# SWR_Tandem_Match.net
KiCad netlist of a schematic drawn in Altium Designer
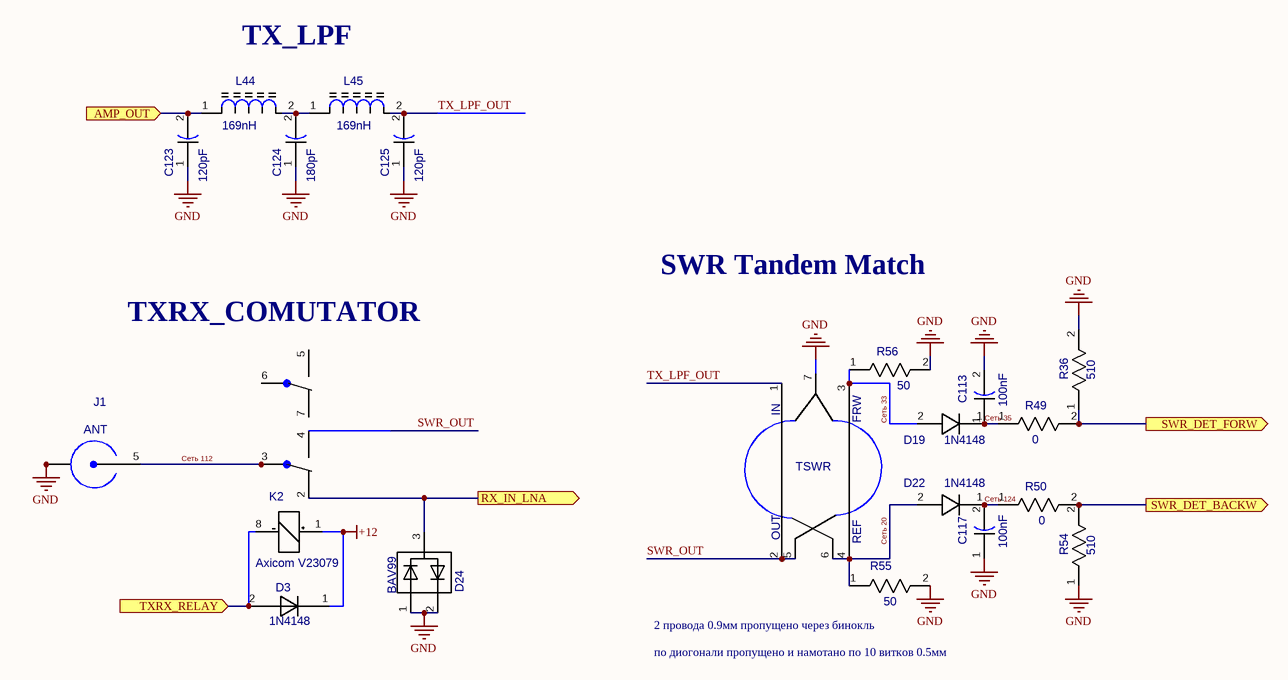
[diagram p0: SWR Tandem Match.SchDoc]

(export (version "E")
  (design (tool "Eeschema 10.0.6"))
  (components
    (comp (ref "C113")
      (value "100nF")
      (footprint "CAP_0805")
      (description "CAP_0805")
      (libsource (lib "*") (part "CAP_0805"))
    )
    (comp (ref "C117")
      (value "100nF")
      (footprint "CAP_0805")
      (description "CAP_0805")
      (libsource (lib "*") (part "CAP_0805"))
    )
    (comp (ref "C123")
      (value "120pF")
      (footprint "CAP_1206")
      (description "CAP_1206")
      (libsource (lib "*") (part "CAP_1206"))
    )
    (comp (ref "C124")
      (value "180pF")
      (footprint "CAP_1206")
      (description "CAP_1206")
      (libsource (lib "*") (part "CAP_1206"))
    )
    (comp (ref "C125")
      (value "120pF")
      (footprint "CAP_1206")
      (description "CAP_1206")
      (libsource (lib "*") (part "CAP_1206"))
    )
    (comp (ref "D3") (value "1N4148") (footprint "1N4148") (libsource (lib "*") (part "1N4148")))
    (comp (ref "D19")
      (value "1N4148")
      (footprint "DIODE_1206")
      (description "DIODE_1206")
      (libsource (lib "*") (part "DIODE_1206"))
    )
    (comp (ref "D22")
      (value "1N4148")
      (footprint "DIODE_1206")
      (description "DIODE_1206")
      (libsource (lib "*") (part "DIODE_1206"))
    )
    (comp (ref "D24") (value "BAV99") (footprint "SOT23") (libsource (lib "*") (part "BAV99")))
    (comp (ref "J1")
      (value "ANT")
      (footprint "31-5431")
      (description "31-5431")
      (libsource (lib "RF-UNIT_1") (part "31-5431"))
    )
    (comp (ref "K2")
      (value "Axicom V23079")
      (footprint "V23079")
      (libsource (lib "RF-UNIT") (part "Axicom V23079"))
    )
    (comp (ref "L44")
      (value "169nH")
      (footprint "IND_FERRITE_CORE_1")
      (description "Inductor")
      (fields (field (name "Comment") "IND_FERRITE_CORE"))
      (libsource (lib "*") (part "IND_FERRITE_CORE"))
    )
    (comp (ref "L45")
      (value "169nH")
      (footprint "IND_FERRITE_CORE_1")
      (description "Inductor")
      (fields (field (name "Comment") "IND_FERRITE_CORE"))
      (libsource (lib "*") (part "IND_FERRITE_CORE"))
    )
    (comp (ref "R36")
      (value "510")
      (footprint "RES_0805")
      (description "RES_0805")
      (libsource (lib "*") (part "RES_0805"))
    )
    (comp (ref "R49")
      (value "0")
      (footprint "RES_0805")
      (description "RES_0805")
      (libsource (lib "*") (part "RES_0805"))
    )
    (comp (ref "R50")
      (value "0")
      (footprint "RES_0805")
      (description "RES_0805")
      (libsource (lib "*") (part "RES_0805"))
    )
    (comp (ref "R54")
      (value "510")
      (footprint "RES_0805")
      (description "RES_0805")
      (libsource (lib "*") (part "RES_0805"))
    )
    (comp (ref "R55")
      (value "50")
      (footprint "RES_1206")
      (description "RES_1206")
      (libsource (lib "*") (part "RES_1206"))
    )
    (comp (ref "R56")
      (value "50")
      (footprint "RES_1206")
      (description "RES_1206")
      (libsource (lib "*") (part "RES_1206"))
    )
    (comp (ref "TSWR")
      (value "SWR_TANDEM_MATCH")
      (footprint "SWR_TANDEM_MATCH")
      (libsource (lib "*") (part "SWR_TANDEM_MATCH"))
    )
  )
  (nets
    (net (code "1") (name "+12") (class "Default")
      (node (ref "D3") (pin "1") (pinfunction "K_1") (pintype "passive"))
      (node (ref "K2") (pin "1") (pinfunction "+_1") (pintype "passive"))
    )
    (net (code "2") (name "/AMP_OUT") (class "Default")
      (node (ref "C123") (pin "2") (pinfunction "2_2") (pintype "passive"))
      (node (ref "L44") (pin "1") (pinfunction "A_1") (pintype "passive"))
    )
    (net (code "3") (name "/RX_IN_LNA") (class "Default")
      (node (ref "D24") (pin "3") (pinfunction "C(D1),A(D2)_3") (pintype "passive"))
      (node (ref "K2") (pin "2") (pinfunction "O_2") (pintype "passive"))
    )
    (net (code "4") (name "/SWR_DET_BACKW") (class "Default")
      (node (ref "R50") (pin "2") (pinfunction "2_2") (pintype "passive"))
      (node (ref "R54") (pin "2") (pinfunction "2_2") (pintype "passive"))
    )
    (net (code "5") (name "/SWR_DET_FORW") (class "Default")
      (node (ref "R36") (pin "1") (pinfunction "1_1") (pintype "passive"))
      (node (ref "R49") (pin "2") (pinfunction "2_2") (pintype "passive"))
    )
    (net (code "6") (name "/SWR_OUT") (class "Default")
      (node (ref "K2") (pin "4") (pinfunction "S_4") (pintype "passive"))
      (node (ref "TSWR") (pin "2") (pinfunction "2_2") (pintype "passive"))
      (node (ref "TSWR") (pin "5") (pinfunction "5_5") (pintype "passive"))
    )
    (net (code "7") (name "/TXRX_RELAY") (class "Default")
      (node (ref "D3") (pin "2") (pinfunction "A_2") (pintype "passive"))
      (node (ref "K2") (pin "8") (pinfunction "-_8") (pintype "passive"))
    )
    (net (code "8") (name "/TX_LPF_OUT") (class "Default")
      (node (ref "C125") (pin "2") (pinfunction "2_2") (pintype "passive"))
      (node (ref "L45") (pin "2") (pinfunction "B_2") (pintype "passive"))
      (node (ref "TSWR") (pin "1") (pinfunction "1_1") (pintype "passive"))
    )
    (net (code "9") (name "/Сеть 20") (class "Default")
      (node (ref "D22") (pin "2") (pinfunction "A_2") (pintype "passive"))
      (node (ref "R55") (pin "1") (pinfunction "1_1") (pintype "passive"))
      (node (ref "TSWR") (pin "4") (pinfunction "4_4") (pintype "passive"))
      (node (ref "TSWR") (pin "6") (pinfunction "6_6") (pintype "passive"))
    )
    (net (code "10") (name "/Сеть 33") (class "Default")
      (node (ref "D19") (pin "2") (pinfunction "A_2") (pintype "passive"))
      (node (ref "R56") (pin "1") (pinfunction "1_1") (pintype "passive"))
      (node (ref "TSWR") (pin "3") (pinfunction "3_3") (pintype "passive"))
    )
    (net (code "11") (name "/Сеть 35") (class "Default")
      (node (ref "C113") (pin "1") (pinfunction "1_1") (pintype "passive"))
      (node (ref "D19") (pin "1") (pinfunction "K_1") (pintype "passive"))
      (node (ref "R49") (pin "1") (pinfunction "1_1") (pintype "passive"))
    )
    (net (code "12") (name "/Сеть 112") (class "Default")
      (node (ref "J1") (pin "5") (pinfunction "CON_5") (pintype "passive"))
      (node (ref "K2") (pin "3") (pinfunction "P_3") (pintype "passive"))
    )
    (net (code "13") (name "/Сеть 124") (class "Default")
      (node (ref "C117") (pin "2") (pinfunction "2_2") (pintype "passive"))
      (node (ref "D22") (pin "1") (pinfunction "K_1") (pintype "passive"))
      (node (ref "R50") (pin "1") (pinfunction "1_1") (pintype "passive"))
    )
    (net (code "14") (name "GND") (class "Default")
      (node (ref "C113") (pin "2") (pinfunction "2_2") (pintype "passive"))
      (node (ref "C117") (pin "1") (pinfunction "1_1") (pintype "passive"))
      (node (ref "C123") (pin "1") (pinfunction "1_1") (pintype "passive"))
      (node (ref "C124") (pin "1") (pinfunction "1_1") (pintype "passive"))
      (node (ref "C125") (pin "1") (pinfunction "1_1") (pintype "passive"))
      (node (ref "D24") (pin "1") (pinfunction "A(D1)_1") (pintype "passive"))
      (node (ref "D24") (pin "2") (pinfunction "C(D2)_2") (pintype "passive"))
      (node (ref "J1") (pin "1") (pinfunction "GND_1") (pintype "passive"))
      (node (ref "J1") (pin "2") (pinfunction "GND_2") (pintype "passive"))
      (node (ref "J1") (pin "3") (pinfunction "GND_3") (pintype "passive"))
      (node (ref "J1") (pin "4") (pinfunction "GND_4") (pintype "passive"))
      (node (ref "R36") (pin "2") (pinfunction "2_2") (pintype "passive"))
      (node (ref "R54") (pin "1") (pinfunction "1_1") (pintype "passive"))
      (node (ref "R55") (pin "2") (pinfunction "2_2") (pintype "passive"))
      (node (ref "R56") (pin "2") (pinfunction "2_2") (pintype "passive"))
      (node (ref "TSWR") (pin "7") (pinfunction "7_7") (pintype "passive"))
    )
    (net (code "15") (name "Net-(L44-B)") (class "Default")
      (node (ref "C124") (pin "2") (pinfunction "2_2") (pintype "passive"))
      (node (ref "L44") (pin "2") (pinfunction "B_2") (pintype "passive"))
      (node (ref "L45") (pin "1") (pinfunction "A_1") (pintype "passive"))
    )
    (net (code "16") (name "unconnected-(K2-O-Pad7)") (class "Default")
      (node (ref "K2") (pin "7") (pinfunction "O_7") (pintype "passive"))
    )
    (net (code "17") (name "unconnected-(K2-P-Pad6)") (class "Default")
      (node (ref "K2") (pin "6") (pinfunction "P_6") (pintype "passive"))
    )
    (net (code "18") (name "unconnected-(K2-S-Pad5)") (class "Default")
      (node (ref "K2") (pin "5") (pinfunction "S_5") (pintype "passive"))
    )
  )
)
